# cs301_Team_15.net
KiCad netlist of a schematic drawn in Altium Designer
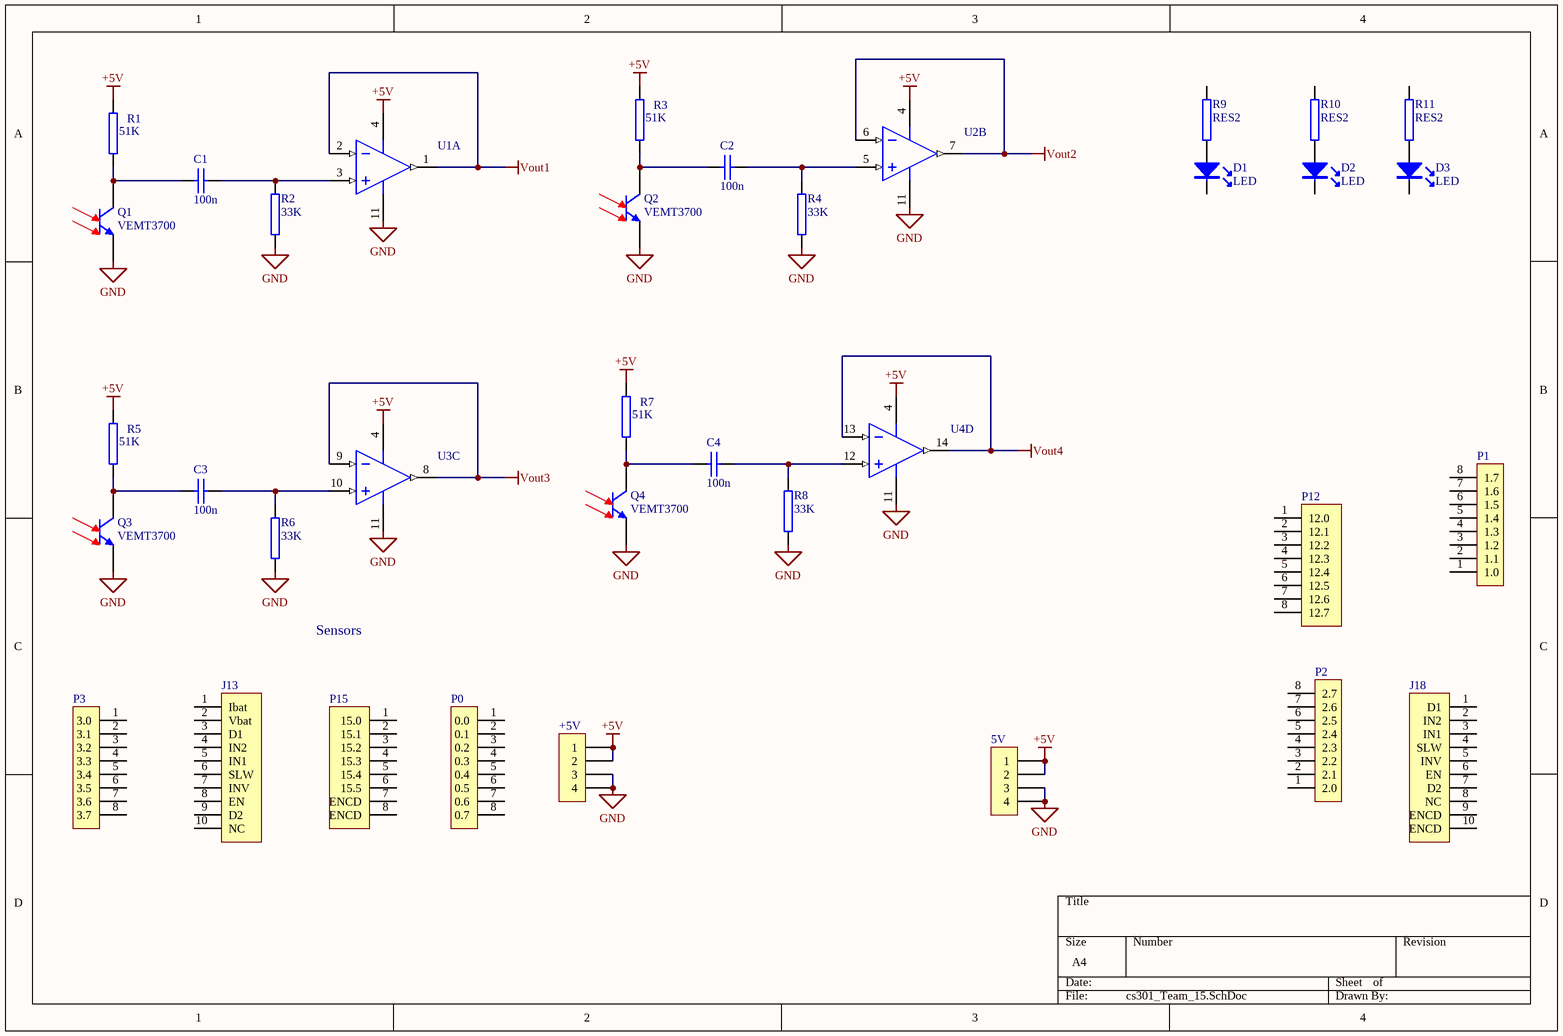
[diagram p0: cs301_Team_15.SchDoc]

(export (version "E")
  (design (tool "Eeschema 10.0.6"))
  (components
    (comp (ref "+5V")
      (value "5V")
      (footprint "IDC4")
      (description "Connector")
      (libsource (lib "Miscellaneous Devices") (part "CON4"))
    )
    (comp (ref "5V")
      (value "5V")
      (footprint "IDC4")
      (description "Connector")
      (libsource (lib "Miscellaneous Devices") (part "CON4"))
    )
    (comp (ref "C1")
      (value "100n")
      (footprint "CCAP-5P0")
      (description "TH ceramic capacitor with 5mm pitch")
      (libsource (lib "EE209_Library") (part "CerCap_TH_5P0"))
    )
    (comp (ref "C2")
      (value "100n")
      (footprint "CCAP-5P0")
      (description "TH ceramic capacitor with 5mm pitch")
      (libsource (lib "EE209_Library") (part "CerCap_TH_5P0"))
    )
    (comp (ref "C3")
      (value "100n")
      (footprint "CCAP-5P0")
      (description "TH ceramic capacitor with 5mm pitch")
      (libsource (lib "EE209_Library") (part "CerCap_TH_5P0"))
    )
    (comp (ref "C4")
      (value "100n")
      (footprint "CCAP-5P0")
      (description "TH ceramic capacitor with 5mm pitch")
      (libsource (lib "EE209_Library") (part "CerCap_TH_5P0"))
    )
    (comp (ref "D1") (value "LED") (footprint "LED0.1/5MM") (libsource (lib "COMSYS301_2013") (part "LED")))
    (comp (ref "D2") (value "LED") (footprint "LED0.1/5MM") (libsource (lib "COMSYS301_2013") (part "LED")))
    (comp (ref "D3") (value "LED") (footprint "LED0.1/5MM") (libsource (lib "COMSYS301_2013") (part "LED")))
    (comp (ref "J13")
      (value "CON10")
      (footprint "idc10")
      (description "Connector")
      (libsource (lib "") (part "CON10_1"))
    )
    (comp (ref "J18")
      (value "CON10")
      (footprint "IDC10")
      (description "Connector")
      (libsource (lib "Miscellaneous Devices") (part "CON10"))
    )
    (comp (ref "P0")
      (value "P0")
      (footprint "idc8")
      (description "Connector")
      (libsource (lib "Miscellaneous Devices") (part "CON8"))
    )
    (comp (ref "P1")
      (value "P1")
      (footprint "idc8")
      (description "Connector")
      (libsource (lib "") (part "CON8_2"))
    )
    (comp (ref "P2")
      (value "P2")
      (footprint "idc8")
      (description "Connector")
      (libsource (lib "") (part "CON8_1"))
    )
    (comp (ref "P3")
      (value "P3")
      (footprint "idc8")
      (description "Connector")
      (libsource (lib "Miscellaneous Devices") (part "CON8"))
    )
    (comp (ref "P12")
      (value "P12")
      (footprint "idc8")
      (description "Connector")
      (libsource (lib "") (part "CON8_1_1"))
    )
    (comp (ref "P15")
      (value "P15")
      (footprint "idc8")
      (description "Connector")
      (libsource (lib "Miscellaneous Devices") (part "CON8_1"))
    )
    (comp (ref "Q1")
      (value "VEMT3700")
      (footprint "VEMT3700")
      (description "Silicon NPN Phototransistor")
      (libsource (lib "COMSYS301_2013") (part "VEMT3700"))
    )
    (comp (ref "Q2")
      (value "VEMT3700")
      (footprint "VEMT3700")
      (description "Silicon NPN Phototransistor")
      (libsource (lib "COMSYS301_2013") (part "VEMT3700"))
    )
    (comp (ref "Q3")
      (value "VEMT3700")
      (footprint "VEMT3700")
      (description "Silicon NPN Phototransistor")
      (libsource (lib "COMSYS301_2013") (part "VEMT3700"))
    )
    (comp (ref "Q4")
      (value "VEMT3700")
      (footprint "VEMT3700")
      (description "Silicon NPN Phototransistor")
      (libsource (lib "COMSYS301_2013") (part "VEMT3700"))
    )
    (comp (ref "R1") (value "51K") (footprint "AXIAL0.4") (libsource (lib "COMSYS301_2013") (part "RES2")))
    (comp (ref "R2") (value "33K") (footprint "AXIAL0.4") (libsource (lib "COMSYS301_2013") (part "RES2")))
    (comp (ref "R3") (value "51K") (footprint "AXIAL0.4") (libsource (lib "COMSYS301_2013") (part "RES2")))
    (comp (ref "R4") (value "33K") (footprint "AXIAL0.4") (libsource (lib "COMSYS301_2013") (part "RES2")))
    (comp (ref "R5") (value "51K") (footprint "AXIAL0.4") (libsource (lib "COMSYS301_2013") (part "RES2")))
    (comp (ref "R6") (value "33K") (footprint "AXIAL0.4") (libsource (lib "COMSYS301_2013") (part "RES2")))
    (comp (ref "R7") (value "51K") (footprint "AXIAL0.4") (libsource (lib "COMSYS301_2013") (part "RES2")))
    (comp (ref "R8") (value "33K") (footprint "AXIAL0.4") (libsource (lib "COMSYS301_2013") (part "RES2")))
    (comp (ref "R9") (value "RES2") (footprint "AXIAL0.4") (libsource (lib "COMSYS301_2013") (part "RES2")))
    (comp (ref "R10") (value "RES2") (footprint "AXIAL0.4") (libsource (lib "COMSYS301_2013") (part "RES2")))
    (comp (ref "R11") (value "RES2") (footprint "AXIAL0.4") (libsource (lib "COMSYS301_2013") (part "RES2")))
    (comp (ref "U1")
      (value "LM324")
      (footprint "DIP-14")
      (description "IC OPAMP GP 14DIP")
      (fields
        (field (name "MANUFACTURER") "ON Semiconductor")
        (field (name "MANUFACTURER PART NUMBER") "LM324N")
      )
      (libsource (lib "EE209_Library") (part "LM324N_TH_DIP16"))
    )
    (comp (ref "U2")
      (value "LM324")
      (footprint "DIP-14")
      (description "IC OPAMP GP 14DIP")
      (fields
        (field (name "MANUFACTURER") "ON Semiconductor")
        (field (name "MANUFACTURER PART NUMBER") "LM324N")
      )
      (libsource (lib "EE209_Library") (part "LM324N_TH_DIP16"))
    )
    (comp (ref "U3")
      (value "LM324")
      (footprint "DIP-14")
      (description "IC OPAMP GP 14DIP")
      (fields
        (field (name "MANUFACTURER") "ON Semiconductor")
        (field (name "MANUFACTURER PART NUMBER") "LM324N")
      )
      (libsource (lib "EE209_Library") (part "LM324N_TH_DIP16"))
    )
    (comp (ref "U4")
      (value "LM324")
      (footprint "DIP-14")
      (description "IC OPAMP GP 14DIP")
      (fields
        (field (name "MANUFACTURER") "ON Semiconductor")
        (field (name "MANUFACTURER PART NUMBER") "LM324N")
      )
      (libsource (lib "EE209_Library") (part "LM324N_TH_DIP16"))
    )
  )
  (nets
    (net (code "1") (name "+5V") (class "Default")
      (node (ref "+5V") (pin "1") (pinfunction "1_1") (pintype "passive"))
      (node (ref "+5V") (pin "2") (pinfunction "2_2") (pintype "passive"))
      (node (ref "5V") (pin "1") (pinfunction "1_1") (pintype "passive"))
      (node (ref "5V") (pin "2") (pinfunction "2_2") (pintype "passive"))
      (node (ref "R1") (pin "2") (pinfunction "2_2") (pintype "passive"))
      (node (ref "R3") (pin "2") (pinfunction "2_2") (pintype "passive"))
      (node (ref "R5") (pin "2") (pinfunction "2_2") (pintype "passive"))
      (node (ref "R7") (pin "2") (pinfunction "2_2") (pintype "passive"))
      (node (ref "U1") (pin "4") (pinfunction "VDD_4") (pintype "power_in"))
      (node (ref "U2") (pin "4") (pinfunction "VDD_4") (pintype "power_in"))
      (node (ref "U3") (pin "4") (pinfunction "VDD_4") (pintype "power_in"))
      (node (ref "U4") (pin "4") (pinfunction "VDD_4") (pintype "power_in"))
    )
    (net (code "2") (name "GND") (class "Default")
      (node (ref "+5V") (pin "3") (pinfunction "3_3") (pintype "passive"))
      (node (ref "+5V") (pin "4") (pinfunction "4_4") (pintype "passive"))
      (node (ref "5V") (pin "3") (pinfunction "3_3") (pintype "passive"))
      (node (ref "5V") (pin "4") (pinfunction "4_4") (pintype "passive"))
      (node (ref "Q1") (pin "2") (pinfunction "E_2") (pintype "passive"))
      (node (ref "Q2") (pin "2") (pinfunction "E_2") (pintype "passive"))
      (node (ref "Q3") (pin "2") (pinfunction "E_2") (pintype "passive"))
      (node (ref "Q4") (pin "2") (pinfunction "E_2") (pintype "passive"))
      (node (ref "R2") (pin "1") (pinfunction "1_1") (pintype "passive"))
      (node (ref "R4") (pin "1") (pinfunction "1_1") (pintype "passive"))
      (node (ref "R6") (pin "1") (pinfunction "1_1") (pintype "passive"))
      (node (ref "R8") (pin "1") (pinfunction "1_1") (pintype "passive"))
      (node (ref "U1") (pin "11") (pinfunction "VSS_11") (pintype "power_in"))
      (node (ref "U2") (pin "11") (pinfunction "VSS_11") (pintype "power_in"))
      (node (ref "U3") (pin "11") (pinfunction "VSS_11") (pintype "power_in"))
      (node (ref "U4") (pin "11") (pinfunction "VSS_11") (pintype "power_in"))
    )
    (net (code "3") (name "Net-(D1-1)") (class "Default")
      (node (ref "D1") (pin "A") (pinfunction "1_A") (pintype "passive"))
      (node (ref "R9") (pin "1") (pinfunction "1_1") (pintype "passive"))
    )
    (net (code "4") (name "Net-(D2-1)") (class "Default")
      (node (ref "D2") (pin "A") (pinfunction "1_A") (pintype "passive"))
      (node (ref "R10") (pin "1") (pinfunction "1_1") (pintype "passive"))
    )
    (net (code "5") (name "Net-(D3-1)") (class "Default")
      (node (ref "D3") (pin "A") (pinfunction "1_A") (pintype "passive"))
      (node (ref "R11") (pin "2") (pinfunction "2_2") (pintype "passive"))
    )
    (net (code "6") (name "Net-(Q1-C)") (class "Default")
      (node (ref "C1") (pin "1") (pinfunction "1_1") (pintype "passive"))
      (node (ref "Q1") (pin "1") (pinfunction "C_1") (pintype "passive"))
      (node (ref "R1") (pin "1") (pinfunction "1_1") (pintype "passive"))
    )
    (net (code "7") (name "Net-(Q2-C)") (class "Default")
      (node (ref "C2") (pin "1") (pinfunction "1_1") (pintype "passive"))
      (node (ref "Q2") (pin "1") (pinfunction "C_1") (pintype "passive"))
      (node (ref "R3") (pin "1") (pinfunction "1_1") (pintype "passive"))
    )
    (net (code "8") (name "Net-(Q3-C)") (class "Default")
      (node (ref "C3") (pin "1") (pinfunction "1_1") (pintype "passive"))
      (node (ref "Q3") (pin "1") (pinfunction "C_1") (pintype "passive"))
      (node (ref "R5") (pin "1") (pinfunction "1_1") (pintype "passive"))
    )
    (net (code "9") (name "Net-(Q4-C)") (class "Default")
      (node (ref "C4") (pin "1") (pinfunction "1_1") (pintype "passive"))
      (node (ref "Q4") (pin "1") (pinfunction "C_1") (pintype "passive"))
      (node (ref "R7") (pin "1") (pinfunction "1_1") (pintype "passive"))
    )
    (net (code "10") (name "Net-(U1A-VINA+)") (class "Default")
      (node (ref "C1") (pin "2") (pinfunction "2_2") (pintype "passive"))
      (node (ref "R2") (pin "2") (pinfunction "2_2") (pintype "passive"))
      (node (ref "U1") (pin "3") (pinfunction "VINA+_3") (pintype "input"))
    )
    (net (code "11") (name "Net-(U2B-VINB+)") (class "Default")
      (node (ref "C2") (pin "2") (pinfunction "2_2") (pintype "passive"))
      (node (ref "R4") (pin "2") (pinfunction "2_2") (pintype "passive"))
      (node (ref "U2") (pin "5") (pinfunction "VINB+_5") (pintype "input"))
    )
    (net (code "12") (name "Net-(U3C-VINC+)") (class "Default")
      (node (ref "C3") (pin "2") (pinfunction "2_2") (pintype "passive"))
      (node (ref "R6") (pin "2") (pinfunction "2_2") (pintype "passive"))
      (node (ref "U3") (pin "10") (pinfunction "VINC+_10") (pintype "input"))
    )
    (net (code "13") (name "Net-(U4D-VIND+)") (class "Default")
      (node (ref "C4") (pin "2") (pinfunction "2_2") (pintype "passive"))
      (node (ref "R8") (pin "2") (pinfunction "2_2") (pintype "passive"))
      (node (ref "U4") (pin "12") (pinfunction "VIND+_12") (pintype "input"))
    )
    (net (code "14") (name "Vout1") (class "Default")
      (node (ref "U1") (pin "1") (pinfunction "VOUTA_1") (pintype "output"))
      (node (ref "U1") (pin "2") (pinfunction "VINA-_2") (pintype "input"))
    )
    (net (code "15") (name "Vout2") (class "Default")
      (node (ref "U2") (pin "6") (pinfunction "VINB-_6") (pintype "input"))
      (node (ref "U2") (pin "7") (pinfunction "VOUTB_7") (pintype "output"))
    )
    (net (code "16") (name "Vout3") (class "Default")
      (node (ref "U3") (pin "8") (pinfunction "VOUTC_8") (pintype "output"))
      (node (ref "U3") (pin "9") (pinfunction "VINC-_9") (pintype "input"))
    )
    (net (code "17") (name "Vout4") (class "Default")
      (node (ref "U4") (pin "13") (pinfunction "VIND-_13") (pintype "input"))
      (node (ref "U4") (pin "14") (pinfunction "VOUTD_14") (pintype "output"))
    )
    (net (code "18") (name "unconnected-(D1-2-PadK)") (class "Default")
      (node (ref "D1") (pin "K") (pinfunction "2_K") (pintype "passive"))
    )
    (net (code "19") (name "unconnected-(D2-2-PadK)") (class "Default")
      (node (ref "D2") (pin "K") (pinfunction "2_K") (pintype "passive"))
    )
    (net (code "20") (name "unconnected-(D3-2-PadK)") (class "Default")
      (node (ref "D3") (pin "K") (pinfunction "2_K") (pintype "passive"))
    )
    (net (code "21") (name "unconnected-(J13-D1-Pad3)") (class "Default")
      (node (ref "J13") (pin "3") (pinfunction "D1_3") (pintype "passive"))
    )
    (net (code "22") (name "unconnected-(J13-D2-Pad9)") (class "Default")
      (node (ref "J13") (pin "9") (pinfunction "D2_9") (pintype "passive"))
    )
    (net (code "23") (name "unconnected-(J13-EN-Pad8)") (class "Default")
      (node (ref "J13") (pin "8") (pinfunction "EN_8") (pintype "passive"))
    )
    (net (code "24") (name "unconnected-(J13-IN1-Pad5)") (class "Default")
      (node (ref "J13") (pin "5") (pinfunction "IN1_5") (pintype "passive"))
    )
    (net (code "25") (name "unconnected-(J13-IN2-Pad4)") (class "Default")
      (node (ref "J13") (pin "4") (pinfunction "IN2_4") (pintype "passive"))
    )
    (net (code "26") (name "unconnected-(J13-INV-Pad7)") (class "Default")
      (node (ref "J13") (pin "7") (pinfunction "INV_7") (pintype "passive"))
    )
    (net (code "27") (name "unconnected-(J13-Ibat-Pad1)") (class "Default")
      (node (ref "J13") (pin "1") (pinfunction "Ibat_1") (pintype "passive"))
    )
    (net (code "28") (name "unconnected-(J13-NC-Pad10)") (class "Default")
      (node (ref "J13") (pin "10") (pinfunction "NC_10") (pintype "passive"))
    )
    (net (code "29") (name "unconnected-(J13-SLW-Pad6)") (class "Default")
      (node (ref "J13") (pin "6") (pinfunction "SLW_6") (pintype "passive"))
    )
    (net (code "30") (name "unconnected-(J13-Vbat-Pad2)") (class "Default")
      (node (ref "J13") (pin "2") (pinfunction "Vbat_2") (pintype "passive"))
    )
    (net (code "31") (name "unconnected-(J18-D1-Pad1)") (class "Default")
      (node (ref "J18") (pin "1") (pinfunction "D1_1") (pintype "passive"))
    )
    (net (code "32") (name "unconnected-(J18-D2-Pad7)") (class "Default")
      (node (ref "J18") (pin "7") (pinfunction "D2_7") (pintype "passive"))
    )
    (net (code "33") (name "unconnected-(J18-EN-Pad6)") (class "Default")
      (node (ref "J18") (pin "6") (pinfunction "EN_6") (pintype "passive"))
    )
    (net (code "34") (name "unconnected-(J18-ENCD-Pad9)") (class "Default")
      (node (ref "J18") (pin "9") (pinfunction "ENCD_9") (pintype "passive"))
    )
    (net (code "35") (name "unconnected-(J18-ENCD-Pad10)") (class "Default")
      (node (ref "J18") (pin "10") (pinfunction "ENCD_10") (pintype "passive"))
    )
    (net (code "36") (name "unconnected-(J18-IN1-Pad3)") (class "Default")
      (node (ref "J18") (pin "3") (pinfunction "IN1_3") (pintype "passive"))
    )
    (net (code "37") (name "unconnected-(J18-IN2-Pad2)") (class "Default")
      (node (ref "J18") (pin "2") (pinfunction "IN2_2") (pintype "passive"))
    )
    (net (code "38") (name "unconnected-(J18-INV-Pad5)") (class "Default")
      (node (ref "J18") (pin "5") (pinfunction "INV_5") (pintype "passive"))
    )
    (net (code "39") (name "unconnected-(J18-NC-Pad8)") (class "Default")
      (node (ref "J18") (pin "8") (pinfunction "NC_8") (pintype "passive"))
    )
    (net (code "40") (name "unconnected-(J18-SLW-Pad4)") (class "Default")
      (node (ref "J18") (pin "4") (pinfunction "SLW_4") (pintype "passive"))
    )
    (net (code "41") (name "unconnected-(P0-3.0-Pad1)") (class "Default")
      (node (ref "P0") (pin "1") (pinfunction "3.0_1") (pintype "passive"))
    )
    (net (code "42") (name "unconnected-(P0-3.1-Pad2)") (class "Default")
      (node (ref "P0") (pin "2") (pinfunction "3.1_2") (pintype "passive"))
    )
    (net (code "43") (name "unconnected-(P0-3.2-Pad3)") (class "Default")
      (node (ref "P0") (pin "3") (pinfunction "3.2_3") (pintype "passive"))
    )
    (net (code "44") (name "unconnected-(P0-3.3-Pad4)") (class "Default")
      (node (ref "P0") (pin "4") (pinfunction "3.3_4") (pintype "passive"))
    )
    (net (code "45") (name "unconnected-(P0-3.4-Pad5)") (class "Default")
      (node (ref "P0") (pin "5") (pinfunction "3.4_5") (pintype "passive"))
    )
    (net (code "46") (name "unconnected-(P0-3.5-Pad6)") (class "Default")
      (node (ref "P0") (pin "6") (pinfunction "3.5_6") (pintype "passive"))
    )
    (net (code "47") (name "unconnected-(P0-3.6-Pad7)") (class "Default")
      (node (ref "P0") (pin "7") (pinfunction "3.6_7") (pintype "passive"))
    )
    (net (code "48") (name "unconnected-(P0-3.7-Pad8)") (class "Default")
      (node (ref "P0") (pin "8") (pinfunction "3.7_8") (pintype "passive"))
    )
    (net (code "49") (name "unconnected-(P1-1.0-Pad1)") (class "Default")
      (node (ref "P1") (pin "1") (pinfunction "1.0_1") (pintype "passive"))
    )
    (net (code "50") (name "unconnected-(P1-1.1-Pad2)") (class "Default")
      (node (ref "P1") (pin "2") (pinfunction "1.1_2") (pintype "passive"))
    )
    (net (code "51") (name "unconnected-(P1-1.2-Pad3)") (class "Default")
      (node (ref "P1") (pin "3") (pinfunction "1.2_3") (pintype "passive"))
    )
    (net (code "52") (name "unconnected-(P1-1.3-Pad4)") (class "Default")
      (node (ref "P1") (pin "4") (pinfunction "1.3_4") (pintype "passive"))
    )
    (net (code "53") (name "unconnected-(P1-1.4-Pad5)") (class "Default")
      (node (ref "P1") (pin "5") (pinfunction "1.4_5") (pintype "passive"))
    )
    (net (code "54") (name "unconnected-(P1-1.5-Pad6)") (class "Default")
      (node (ref "P1") (pin "6") (pinfunction "1.5_6") (pintype "passive"))
    )
    (net (code "55") (name "unconnected-(P1-1.6-Pad7)") (class "Default")
      (node (ref "P1") (pin "7") (pinfunction "1.6_7") (pintype "passive"))
    )
    (net (code "56") (name "unconnected-(P1-1.7-Pad8)") (class "Default")
      (node (ref "P1") (pin "8") (pinfunction "1.7_8") (pintype "passive"))
    )
    (net (code "57") (name "unconnected-(P2-2.0-Pad1)") (class "Default")
      (node (ref "P2") (pin "1") (pinfunction "2.0_1") (pintype "passive"))
    )
    (net (code "58") (name "unconnected-(P2-2.1-Pad2)") (class "Default")
      (node (ref "P2") (pin "2") (pinfunction "2.1_2") (pintype "passive"))
    )
    (net (code "59") (name "unconnected-(P2-2.2-Pad3)") (class "Default")
      (node (ref "P2") (pin "3") (pinfunction "2.2_3") (pintype "passive"))
    )
    (net (code "60") (name "unconnected-(P2-2.3-Pad4)") (class "Default")
      (node (ref "P2") (pin "4") (pinfunction "2.3_4") (pintype "passive"))
    )
    (net (code "61") (name "unconnected-(P2-2.4-Pad5)") (class "Default")
      (node (ref "P2") (pin "5") (pinfunction "2.4_5") (pintype "passive"))
    )
    (net (code "62") (name "unconnected-(P2-2.5-Pad6)") (class "Default")
      (node (ref "P2") (pin "6") (pinfunction "2.5_6") (pintype "passive"))
    )
    (net (code "63") (name "unconnected-(P2-2.6-Pad7)") (class "Default")
      (node (ref "P2") (pin "7") (pinfunction "2.6_7") (pintype "passive"))
    )
    (net (code "64") (name "unconnected-(P2-2.7-Pad8)") (class "Default")
      (node (ref "P2") (pin "8") (pinfunction "2.7_8") (pintype "passive"))
    )
    (net (code "65") (name "unconnected-(P3-3.0-Pad1)") (class "Default")
      (node (ref "P3") (pin "1") (pinfunction "3.0_1") (pintype "passive"))
    )
    (net (code "66") (name "unconnected-(P3-3.1-Pad2)") (class "Default")
      (node (ref "P3") (pin "2") (pinfunction "3.1_2") (pintype "passive"))
    )
    (net (code "67") (name "unconnected-(P3-3.2-Pad3)") (class "Default")
      (node (ref "P3") (pin "3") (pinfunction "3.2_3") (pintype "passive"))
    )
    (net (code "68") (name "unconnected-(P3-3.3-Pad4)") (class "Default")
      (node (ref "P3") (pin "4") (pinfunction "3.3_4") (pintype "passive"))
    )
    (net (code "69") (name "unconnected-(P3-3.4-Pad5)") (class "Default")
      (node (ref "P3") (pin "5") (pinfunction "3.4_5") (pintype "passive"))
    )
    (net (code "70") (name "unconnected-(P3-3.5-Pad6)") (class "Default")
      (node (ref "P3") (pin "6") (pinfunction "3.5_6") (pintype "passive"))
    )
    (net (code "71") (name "unconnected-(P3-3.6-Pad7)") (class "Default")
      (node (ref "P3") (pin "7") (pinfunction "3.6_7") (pintype "passive"))
    )
    (net (code "72") (name "unconnected-(P3-3.7-Pad8)") (class "Default")
      (node (ref "P3") (pin "8") (pinfunction "3.7_8") (pintype "passive"))
    )
    (net (code "73") (name "unconnected-(P12-12.0-Pad1)") (class "Default")
      (node (ref "P12") (pin "1") (pinfunction "12.0_1") (pintype "passive"))
    )
    (net (code "74") (name "unconnected-(P12-12.1-Pad2)") (class "Default")
      (node (ref "P12") (pin "2") (pinfunction "12.1_2") (pintype "passive"))
    )
    (net (code "75") (name "unconnected-(P12-12.2-Pad3)") (class "Default")
      (node (ref "P12") (pin "3") (pinfunction "12.2_3") (pintype "passive"))
    )
    (net (code "76") (name "unconnected-(P12-12.3-Pad4)") (class "Default")
      (node (ref "P12") (pin "4") (pinfunction "12.3_4") (pintype "passive"))
    )
    (net (code "77") (name "unconnected-(P12-12.4-Pad5)") (class "Default")
      (node (ref "P12") (pin "5") (pinfunction "12.4_5") (pintype "passive"))
    )
    (net (code "78") (name "unconnected-(P12-12.5-Pad6)") (class "Default")
      (node (ref "P12") (pin "6") (pinfunction "12.5_6") (pintype "passive"))
    )
    (net (code "79") (name "unconnected-(P12-12.6-Pad7)") (class "Default")
      (node (ref "P12") (pin "7") (pinfunction "12.6_7") (pintype "passive"))
    )
    (net (code "80") (name "unconnected-(P12-12.7-Pad8)") (class "Default")
      (node (ref "P12") (pin "8") (pinfunction "12.7_8") (pintype "passive"))
    )
    (net (code "81") (name "unconnected-(P15-15.0-Pad1)") (class "Default")
      (node (ref "P15") (pin "1") (pinfunction "15.0_1") (pintype "passive"))
    )
    (net (code "82") (name "unconnected-(P15-15.1-Pad2)") (class "Default")
      (node (ref "P15") (pin "2") (pinfunction "15.1_2") (pintype "passive"))
    )
    (net (code "83") (name "unconnected-(P15-15.2-Pad3)") (class "Default")
      (node (ref "P15") (pin "3") (pinfunction "15.2_3") (pintype "passive"))
    )
    (net (code "84") (name "unconnected-(P15-15.3-Pad4)") (class "Default")
      (node (ref "P15") (pin "4") (pinfunction "15.3_4") (pintype "passive"))
    )
    (net (code "85") (name "unconnected-(P15-15.4-Pad5)") (class "Default")
      (node (ref "P15") (pin "5") (pinfunction "15.4_5") (pintype "passive"))
    )
    (net (code "86") (name "unconnected-(P15-15.5-Pad6)") (class "Default")
      (node (ref "P15") (pin "6") (pinfunction "15.5_6") (pintype "passive"))
    )
    (net (code "87") (name "unconnected-(P15-ENCD-Pad7)") (class "Default")
      (node (ref "P15") (pin "7") (pinfunction "ENCD_7") (pintype "passive"))
    )
    (net (code "88") (name "unconnected-(P15-ENCD-Pad8)") (class "Default")
      (node (ref "P15") (pin "8") (pinfunction "ENCD_8") (pintype "passive"))
    )
    (net (code "89") (name "unconnected-(R9-Pad2)") (class "Default")
      (node (ref "R9") (pin "2") (pinfunction "2_2") (pintype "passive"))
    )
    (net (code "90") (name "unconnected-(R10-Pad2)") (class "Default")
      (node (ref "R10") (pin "2") (pinfunction "2_2") (pintype "passive"))
    )
    (net (code "91") (name "unconnected-(R11-Pad1)") (class "Default")
      (node (ref "R11") (pin "1") (pinfunction "1_1") (pintype "passive"))
    )
  )
)
